# Robert_Sullivan_touch.net
KiCad netlist of a schematic drawn in EAGLE
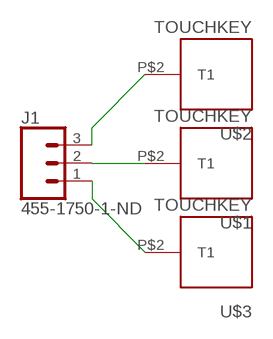
[diagram p0: schematic, sheet 1]

(export (version "E")
  (design (tool "Eeschema 10.0.6"))
  (components
    (comp (ref "J1")
      (value "455-1750-1-ND")
      (footprint "eagle-import:1X03")
      (libsource (lib "eagle-import") (part "CONN_03"))
    )
    (comp (ref "U$1")
      (value "TOUCHKEY")
      (footprint "eagle-import:TOUCHPAD")
      (libsource (lib "eagle-import") (part "TOUCHKEY"))
    )
    (comp (ref "U$2")
      (value "TOUCHKEY")
      (footprint "eagle-import:TOUCHPAD")
      (libsource (lib "eagle-import") (part "TOUCHKEY"))
    )
    (comp (ref "U$3")
      (value "TOUCHKEY")
      (footprint "eagle-import:TOUCHPAD")
      (libsource (lib "eagle-import") (part "TOUCHKEY"))
    )
  )
  (nets
    (net (code "1") (name "Net-(U$1-T1)") (class "Default")
      (node (ref "J1") (pin "2") (pinfunction "2_2") (pintype "passive"))
      (node (ref "U$1") (pin "P$2") (pinfunction "T1_P$2") (pintype "bidirectional"))
    )
    (net (code "2") (name "Net-(U$2-T1)") (class "Default")
      (node (ref "J1") (pin "3") (pinfunction "3_3") (pintype "passive"))
      (node (ref "U$2") (pin "P$2") (pinfunction "T1_P$2") (pintype "bidirectional"))
    )
    (net (code "3") (name "Net-(U$3-T1)") (class "Default")
      (node (ref "J1") (pin "1") (pinfunction "1_1") (pintype "passive"))
      (node (ref "U$3") (pin "P$2") (pinfunction "T1_P$2") (pintype "bidirectional"))
    )
  )
)
